# BaseFunctions.net
KiCad netlist of a schematic drawn in Altium Designer
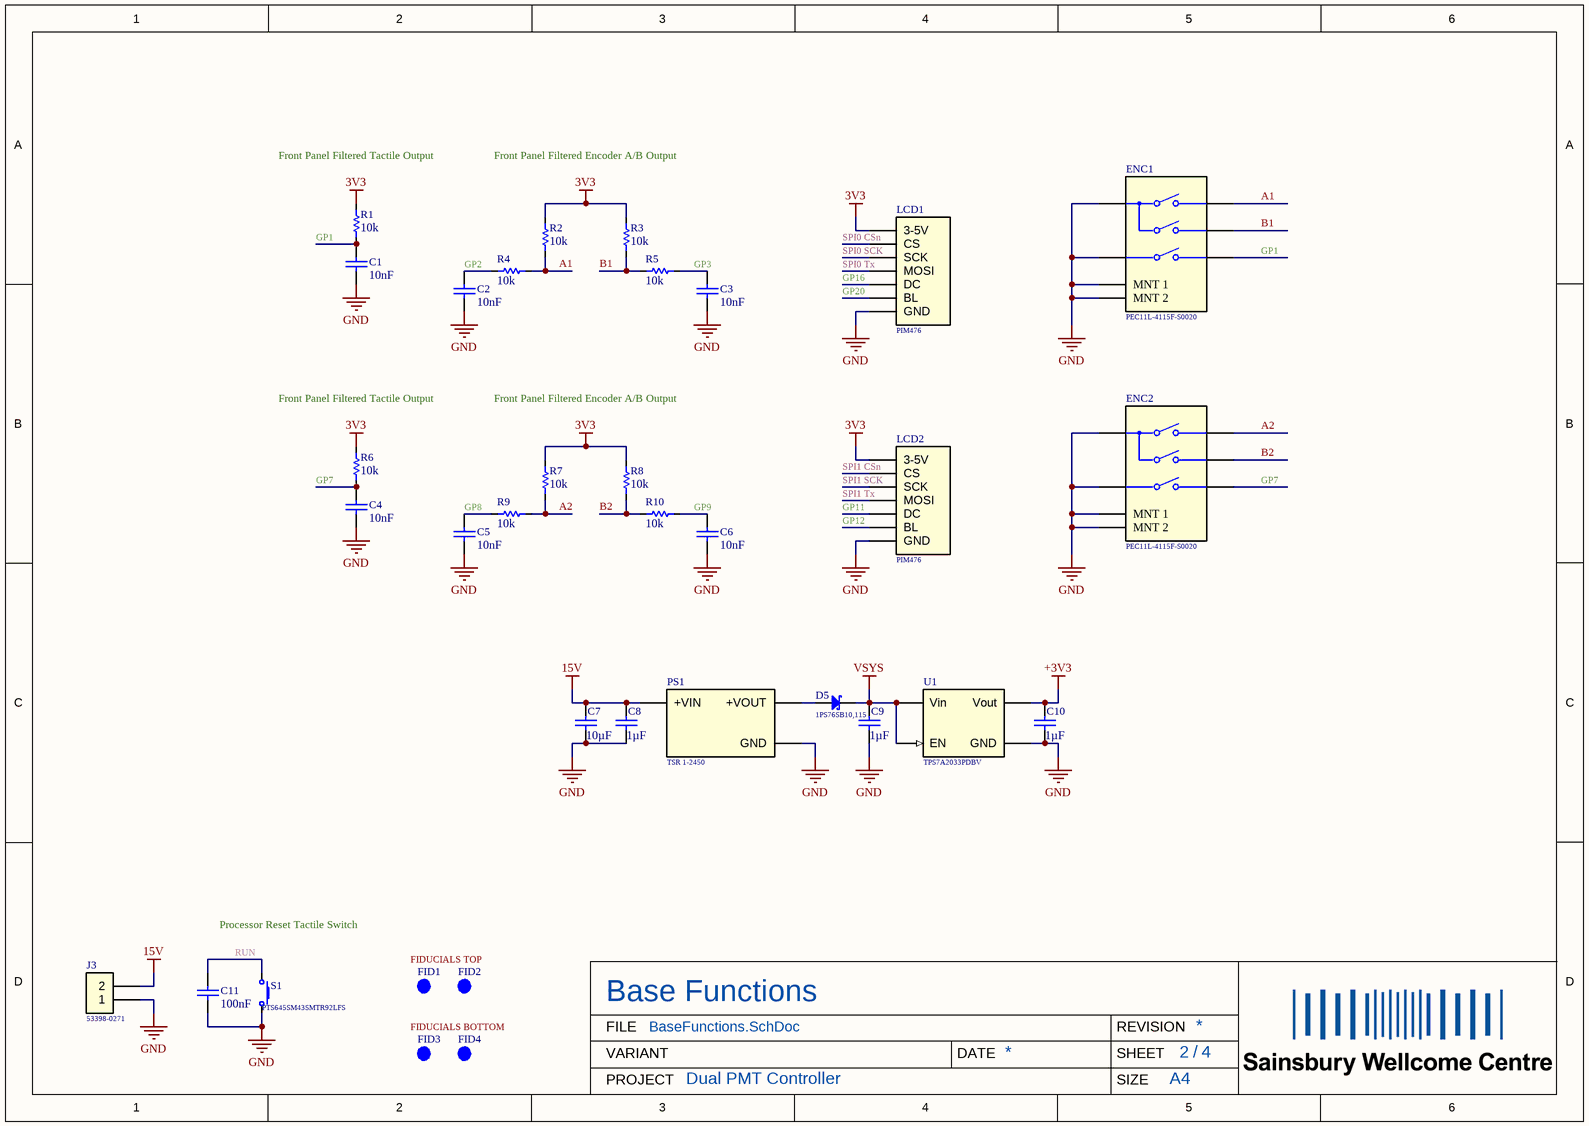
[diagram p0: BaseFunctions.SchDoc]

(export (version "E")
  (design (tool "Eeschema 10.0.6"))
  (components
    (comp (ref "C1")
      (value "10nF")
      (footprint "CAPC1608X90X35NL15T15")
      (description "0.01µF ±10% 100V Ceramic Capacitor X7R 0603 (1608 Metric)")
      (fields (field (name "TOLERANCE") "10%") (field (name "Comment") "C0603-10nF-100V-10%-X7R"))
      (libsource (lib "Sainsbury Wellcome Centre") (part "Cap"))
    )
    (comp (ref "C2")
      (value "10nF")
      (footprint "CAPC1608X90X35NL15T15")
      (description "0.01µF ±10% 100V Ceramic Capacitor X7R 0603 (1608 Metric)")
      (fields (field (name "TOLERANCE") "10%") (field (name "Comment") "C0603-10nF-100V-10%-X7R"))
      (libsource (lib "Sainsbury Wellcome Centre") (part "Cap"))
    )
    (comp (ref "C3")
      (value "10nF")
      (footprint "CAPC1608X90X35NL15T15")
      (description "0.01µF ±10% 100V Ceramic Capacitor X7R 0603 (1608 Metric)")
      (fields (field (name "TOLERANCE") "10%") (field (name "Comment") "C0603-10nF-100V-10%-X7R"))
      (libsource (lib "Sainsbury Wellcome Centre") (part "Cap"))
    )
    (comp (ref "C4")
      (value "10nF")
      (footprint "CAPC1608X90X35NL15T15")
      (description "0.01µF ±10% 100V Ceramic Capacitor X7R 0603 (1608 Metric)")
      (fields (field (name "TOLERANCE") "10%") (field (name "Comment") "C0603-10nF-100V-10%-X7R"))
      (libsource (lib "Sainsbury Wellcome Centre") (part "Cap"))
    )
    (comp (ref "C5")
      (value "10nF")
      (footprint "CAPC1608X90X35NL15T15")
      (description "0.01µF ±10% 100V Ceramic Capacitor X7R 0603 (1608 Metric)")
      (fields (field (name "TOLERANCE") "10%") (field (name "Comment") "C0603-10nF-100V-10%-X7R"))
      (libsource (lib "Sainsbury Wellcome Centre") (part "Cap"))
    )
    (comp (ref "C6")
      (value "10nF")
      (footprint "CAPC1608X90X35NL15T15")
      (description "0.01µF ±10% 100V Ceramic Capacitor X7R 0603 (1608 Metric)")
      (fields (field (name "TOLERANCE") "10%") (field (name "Comment") "C0603-10nF-100V-10%-X7R"))
      (libsource (lib "Sainsbury Wellcome Centre") (part "Cap"))
    )
    (comp (ref "C7")
      (value "10µF")
      (footprint "CAPC3225X279X50NL20T25")
      (description "10uF ±10% 50V Ceramic Capacitor X7R 1210 (3225 Metric)")
      (fields (field (name "TOLERANCE") "10%") (field (name "Comment") "C1210-10uF-50V-10%-X7R"))
      (libsource (lib "Sainsbury Wellcome Centre") (part "Cap"))
    )
    (comp (ref "C8")
      (value "1µF")
      (footprint "FP-GRM188-0_1-e0_2_0_5-IPC_B")
      (description "1µF ±10% 25V Ceramic Capacitor X7R 0603 (1608 Metric)")
      (fields (field (name "TOLERANCE") "10%") (field (name "VOLTAGE") "25V"))
      (libsource (lib "Sainsbury Wellcome Centre") (part "Cap"))
    )
    (comp (ref "C9")
      (value "1µF")
      (footprint "FP-GRM188-0_1-e0_2_0_5-IPC_B")
      (description "1µF ±10% 25V Ceramic Capacitor X7R 0603 (1608 Metric)")
      (fields (field (name "TOLERANCE") "10%") (field (name "VOLTAGE") "25V"))
      (libsource (lib "Sainsbury Wellcome Centre") (part "Cap"))
    )
    (comp (ref "C10")
      (value "1µF")
      (footprint "FP-GRM188-0_1-e0_2_0_5-IPC_B")
      (description "1µF ±10% 25V Ceramic Capacitor X7R 0603 (1608 Metric)")
      (fields (field (name "TOLERANCE") "10%") (field (name "VOLTAGE") "25V"))
      (libsource (lib "Sainsbury Wellcome Centre") (part "Cap"))
    )
    (comp (ref "C11")
      (value "100nF")
      (footprint "FP-GRM188-0_1-e0_2_0_5-IPC_B")
      (description "0.1µF ±10% 100V Ceramic Capacitor X7R 0603 (1608 Metric)")
      (fields (field (name "TOLERANCE") "10%") (field (name "VOLTAGE") "100V"))
      (libsource (lib "Sainsbury Wellcome Centre") (part "Cap"))
    )
    (comp (ref "D5")
      (value "1PS76SB10,115")
      (footprint "FP-SOD323F-MFG")
      (description "Rectifier Diode, Schottky, 1 Phase, 1 Element, 0.2A, Silicon")
      (fields (field (name "PARTNUMBER") "1PS76SB10,115"))
      (libsource (lib "Sainsbury Wellcome Centre") (part "Schottky-C1A2"))
    )
    (comp (ref "ENC1")
      (value "PEC11L-4115F-S0020")
      (footprint "FP-PEC11L-4115F-S0020-MFG")
      (description "LOW PROFILE ENCODER, 11 MM, CONTACT RATING 10 MA - 5 VDC")
      (libsource (lib "Sainsbury Wellcome Centre") (part "PEC11L-4xxxF-Sxxxx"))
    )
    (comp (ref "ENC2")
      (value "PEC11L-4115F-S0020")
      (footprint "FP-PEC11L-4115F-S0020-MFG")
      (description "LOW PROFILE ENCODER, 11 MM, CONTACT RATING 10 MA - 5 VDC")
      (libsource (lib "Sainsbury Wellcome Centre") (part "PEC11L-4xxxF-Sxxxx"))
    )
    (comp (ref "FID1")
      (value "FID-ROUND")
      (footprint "Fid_Round")
      (description "Round Fiducial")
      (libsource (lib "Sainsbury Wellcome Centre") (part "Fid_Round"))
    )
    (comp (ref "FID2")
      (value "FID-ROUND")
      (footprint "Fid_Round")
      (description "Round Fiducial")
      (libsource (lib "Sainsbury Wellcome Centre") (part "Fid_Round"))
    )
    (comp (ref "FID3")
      (value "FID-ROUND")
      (footprint "Fid_Round")
      (description "Round Fiducial")
      (libsource (lib "Sainsbury Wellcome Centre") (part "Fid_Round"))
    )
    (comp (ref "FID4")
      (value "FID-ROUND")
      (footprint "Fid_Round")
      (description "Round Fiducial")
      (libsource (lib "Sainsbury Wellcome Centre") (part "Fid_Round"))
    )
    (comp (ref "J3")
      (value "53398-0271")
      (footprint "MOLX-53398-0271_V")
      (libsource (lib "Sainsbury Wellcome Centre") (part "Jack 2x1"))
    )
    (comp (ref "LCD1")
      (value "PIM476")
      (footprint "LCD-PIM476-TSW - 2mm9 standoff")
      (description "1.3\" Spi Colour Lcd (240X240) Breakout")
      (libsource (lib "Sainsbury Wellcome Centre") (part "LCD-PIM476"))
    )
    (comp (ref "LCD2")
      (value "PIM476")
      (footprint "LCD-PIM476-TSW - 2mm9 standoff")
      (description "1.3\" Spi Colour Lcd (240X240) Breakout")
      (libsource (lib "Sainsbury Wellcome Centre") (part "LCD-PIM476"))
    )
    (comp (ref "PS1")
      (value "TSR 1-2450")
      (footprint "CONV_TSR_1-2433")
      (description "DC/DC Converter, ITE, 1 Output, 5 W, 5 V, 1 A, TSR 1 Series")
      (libsource (lib "Sainsbury Wellcome Centre") (part "TRACO-TSR1-2433-SIP-3"))
    )
    (comp (ref "R1")
      (value "10k")
      (footprint "FP-CPF0603-IPC_B")
      (description "Surface Mount Resistor 10k Ohm 1/16 W 0.1% 0603 (1608 Metric)")
      (fields (field (name "TOLERANCE") "0.1%") (field (name "Comment") "R0603-10k-1/16W-0.1%"))
      (libsource (lib "Sainsbury Wellcome Centre") (part "Res"))
    )
    (comp (ref "R2")
      (value "10k")
      (footprint "FP-CPF0603-IPC_B")
      (description "Surface Mount Resistor 10k Ohm 1/16 W 0.1% 0603 (1608 Metric)")
      (fields (field (name "TOLERANCE") "0.1%") (field (name "Comment") "R0603-10k-1/16W-0.1%"))
      (libsource (lib "Sainsbury Wellcome Centre") (part "Res"))
    )
    (comp (ref "R3")
      (value "10k")
      (footprint "FP-CPF0603-IPC_B")
      (description "Surface Mount Resistor 10k Ohm 1/16 W 0.1% 0603 (1608 Metric)")
      (fields (field (name "TOLERANCE") "0.1%") (field (name "Comment") "R0603-10k-1/16W-0.1%"))
      (libsource (lib "Sainsbury Wellcome Centre") (part "Res"))
    )
    (comp (ref "R4")
      (value "10k")
      (footprint "FP-CPF0603-IPC_B")
      (description "Surface Mount Resistor 10k Ohm 1/16 W 0.1% 0603 (1608 Metric)")
      (fields (field (name "TOLERANCE") "0.1%") (field (name "Comment") "R0603-10k-1/16W-0.1%"))
      (libsource (lib "Sainsbury Wellcome Centre") (part "Res"))
    )
    (comp (ref "R5")
      (value "10k")
      (footprint "FP-CPF0603-IPC_B")
      (description "Surface Mount Resistor 10k Ohm 1/16 W 0.1% 0603 (1608 Metric)")
      (fields (field (name "TOLERANCE") "0.1%") (field (name "Comment") "R0603-10k-1/16W-0.1%"))
      (libsource (lib "Sainsbury Wellcome Centre") (part "Res"))
    )
    (comp (ref "R6")
      (value "10k")
      (footprint "FP-CPF0603-IPC_B")
      (description "Surface Mount Resistor 10k Ohm 1/16 W 0.1% 0603 (1608 Metric)")
      (fields (field (name "TOLERANCE") "0.1%") (field (name "Comment") "R0603-10k-1/16W-0.1%"))
      (libsource (lib "Sainsbury Wellcome Centre") (part "Res"))
    )
    (comp (ref "R7")
      (value "10k")
      (footprint "FP-CPF0603-IPC_B")
      (description "Surface Mount Resistor 10k Ohm 1/16 W 0.1% 0603 (1608 Metric)")
      (fields (field (name "TOLERANCE") "0.1%") (field (name "Comment") "R0603-10k-1/16W-0.1%"))
      (libsource (lib "Sainsbury Wellcome Centre") (part "Res"))
    )
    (comp (ref "R8")
      (value "10k")
      (footprint "FP-CPF0603-IPC_B")
      (description "Surface Mount Resistor 10k Ohm 1/16 W 0.1% 0603 (1608 Metric)")
      (fields (field (name "TOLERANCE") "0.1%") (field (name "Comment") "R0603-10k-1/16W-0.1%"))
      (libsource (lib "Sainsbury Wellcome Centre") (part "Res"))
    )
    (comp (ref "R9")
      (value "10k")
      (footprint "FP-CPF0603-IPC_B")
      (description "Surface Mount Resistor 10k Ohm 1/16 W 0.1% 0603 (1608 Metric)")
      (fields (field (name "TOLERANCE") "0.1%") (field (name "Comment") "R0603-10k-1/16W-0.1%"))
      (libsource (lib "Sainsbury Wellcome Centre") (part "Res"))
    )
    (comp (ref "R10")
      (value "10k")
      (footprint "FP-CPF0603-IPC_B")
      (description "Surface Mount Resistor 10k Ohm 1/16 W 0.1% 0603 (1608 Metric)")
      (fields (field (name "TOLERANCE") "0.1%") (field (name "Comment") "R0603-10k-1/16W-0.1%"))
      (libsource (lib "Sainsbury Wellcome Centre") (part "Res"))
    )
    (comp (ref "S1")
      (value "PTS645SM43SMTR92LFS")
      (footprint "FP-PTS645SM43SMTR92LFS-MFG")
      (libsource (lib "Sainsbury Wellcome Centre") (part "Tactile Switch SPST N.O."))
    )
    (comp (ref "U1")
      (value "TPS7A2033PDBV")
      (footprint "FP-DBV0005A-IPC_B")
      (description "Fixed Positive LDO Regulator, 3.3V, 0.14V Dropout, PDSO5")
      (libsource (lib "Sainsbury Wellcome Centre") (part "TPS7A2033PDBV"))
    )
  )
  (nets
    (net (code "1") (name "+3V3") (class "Default")
      (node (ref "C10") (pin "2") (pinfunction "2_2") (pintype "passive"))
      (node (ref "U1") (pin "5") (pinfunction "Vout_5") (pintype "power_in"))
    )
    (net (code "2") (name "/A1") (class "Default")
      (node (ref "ENC1") (pin "A") (pinfunction "CHANNEL_A_A") (pintype "passive"))
      (node (ref "R2") (pin "1") (pinfunction "1_1") (pintype "passive"))
      (node (ref "R4") (pin "1") (pinfunction "1_1") (pintype "passive"))
    )
    (net (code "3") (name "/A2") (class "Default")
      (node (ref "ENC2") (pin "A") (pinfunction "CHANNEL_A_A") (pintype "passive"))
      (node (ref "R7") (pin "1") (pinfunction "1_1") (pintype "passive"))
      (node (ref "R9") (pin "1") (pinfunction "1_1") (pintype "passive"))
    )
    (net (code "4") (name "/B1") (class "Default")
      (node (ref "ENC1") (pin "B") (pinfunction "CHANNEL_B_B") (pintype "passive"))
      (node (ref "R3") (pin "1") (pinfunction "1_1") (pintype "passive"))
      (node (ref "R5") (pin "2") (pinfunction "2_2") (pintype "passive"))
    )
    (net (code "5") (name "/B2") (class "Default")
      (node (ref "ENC2") (pin "B") (pinfunction "CHANNEL_B_B") (pintype "passive"))
      (node (ref "R10") (pin "2") (pinfunction "2_2") (pintype "passive"))
      (node (ref "R8") (pin "1") (pinfunction "1_1") (pintype "passive"))
    )
    (net (code "6") (name "/GP1") (class "Default")
      (node (ref "C1") (pin "2") (pinfunction "2_2") (pintype "passive"))
      (node (ref "ENC1") (pin "2") (pinfunction "2_2") (pintype "passive"))
      (node (ref "R1") (pin "1") (pinfunction "1_1") (pintype "passive"))
    )
    (net (code "7") (name "/GP2") (class "Default")
      (node (ref "C2") (pin "2") (pinfunction "2_2") (pintype "passive"))
      (node (ref "R4") (pin "2") (pinfunction "2_2") (pintype "passive"))
    )
    (net (code "8") (name "/GP3") (class "Default")
      (node (ref "C3") (pin "2") (pinfunction "2_2") (pintype "passive"))
      (node (ref "R5") (pin "1") (pinfunction "1_1") (pintype "passive"))
    )
    (net (code "9") (name "/GP7") (class "Default")
      (node (ref "C4") (pin "2") (pinfunction "2_2") (pintype "passive"))
      (node (ref "ENC2") (pin "2") (pinfunction "2_2") (pintype "passive"))
      (node (ref "R6") (pin "1") (pinfunction "1_1") (pintype "passive"))
    )
    (net (code "10") (name "/GP8") (class "Default")
      (node (ref "C5") (pin "2") (pinfunction "2_2") (pintype "passive"))
      (node (ref "R9") (pin "2") (pinfunction "2_2") (pintype "passive"))
    )
    (net (code "11") (name "/GP9") (class "Default")
      (node (ref "C6") (pin "2") (pinfunction "2_2") (pintype "passive"))
      (node (ref "R10") (pin "1") (pinfunction "1_1") (pintype "passive"))
    )
    (net (code "12") (name "/GP11") (class "Default")
      (node (ref "LCD2") (pin "5") (pinfunction "DC_5") (pintype "passive"))
    )
    (net (code "13") (name "/GP12") (class "Default")
      (node (ref "LCD2") (pin "6") (pinfunction "BL_6") (pintype "passive"))
    )
    (net (code "14") (name "/GP16") (class "Default")
      (node (ref "LCD1") (pin "5") (pinfunction "DC_5") (pintype "passive"))
    )
    (net (code "15") (name "/GP20") (class "Default")
      (node (ref "LCD1") (pin "6") (pinfunction "BL_6") (pintype "passive"))
    )
    (net (code "16") (name "/RUN") (class "Default")
      (node (ref "C11") (pin "2") (pinfunction "2_2") (pintype "passive"))
      (node (ref "S1") (pin "2") (pinfunction "2_2") (pintype "passive"))
    )
    (net (code "17") (name "/SPI0 CSn") (class "Default")
      (node (ref "LCD1") (pin "2") (pinfunction "CS_2") (pintype "passive"))
    )
    (net (code "18") (name "/SPI0 SCK") (class "Default")
      (node (ref "LCD1") (pin "3") (pinfunction "SCK_3") (pintype "passive"))
    )
    (net (code "19") (name "/SPI0 Tx") (class "Default")
      (node (ref "LCD1") (pin "4") (pinfunction "MOSI_4") (pintype "passive"))
    )
    (net (code "20") (name "/SPI1 CSn") (class "Default")
      (node (ref "LCD2") (pin "2") (pinfunction "CS_2") (pintype "passive"))
    )
    (net (code "21") (name "/SPI1 SCK") (class "Default")
      (node (ref "LCD2") (pin "3") (pinfunction "SCK_3") (pintype "passive"))
    )
    (net (code "22") (name "/SPI1 Tx") (class "Default")
      (node (ref "LCD2") (pin "4") (pinfunction "MOSI_4") (pintype "passive"))
    )
    (net (code "23") (name "3V3") (class "Default")
      (node (ref "LCD1") (pin "1") (pinfunction "3-5V_1") (pintype "passive"))
      (node (ref "LCD2") (pin "1") (pinfunction "3-5V_1") (pintype "passive"))
      (node (ref "R1") (pin "2") (pinfunction "2_2") (pintype "passive"))
      (node (ref "R2") (pin "2") (pinfunction "2_2") (pintype "passive"))
      (node (ref "R3") (pin "2") (pinfunction "2_2") (pintype "passive"))
      (node (ref "R6") (pin "2") (pinfunction "2_2") (pintype "passive"))
      (node (ref "R7") (pin "2") (pinfunction "2_2") (pintype "passive"))
      (node (ref "R8") (pin "2") (pinfunction "2_2") (pintype "passive"))
    )
    (net (code "24") (name "15V") (class "Default")
      (node (ref "C7") (pin "2") (pinfunction "2_2") (pintype "passive"))
      (node (ref "C8") (pin "2") (pinfunction "2_2") (pintype "passive"))
      (node (ref "J3") (pin "2") (pinfunction "2_2") (pintype "passive"))
      (node (ref "PS1") (pin "1") (pinfunction "+VIN_1") (pintype "power_in"))
    )
    (net (code "25") (name "GND") (class "Default")
      (node (ref "C1") (pin "1") (pinfunction "1_1") (pintype "passive"))
      (node (ref "C10") (pin "1") (pinfunction "1_1") (pintype "passive"))
      (node (ref "C11") (pin "1") (pinfunction "1_1") (pintype "passive"))
      (node (ref "C2") (pin "1") (pinfunction "1_1") (pintype "passive"))
      (node (ref "C3") (pin "1") (pinfunction "1_1") (pintype "passive"))
      (node (ref "C4") (pin "1") (pinfunction "1_1") (pintype "passive"))
      (node (ref "C5") (pin "1") (pinfunction "1_1") (pintype "passive"))
      (node (ref "C6") (pin "1") (pinfunction "1_1") (pintype "passive"))
      (node (ref "C7") (pin "1") (pinfunction "1_1") (pintype "passive"))
      (node (ref "C8") (pin "1") (pinfunction "1_1") (pintype "passive"))
      (node (ref "C9") (pin "1") (pinfunction "1_1") (pintype "passive"))
      (node (ref "ENC1") (pin "1") (pinfunction "1_1") (pintype "passive"))
      (node (ref "ENC1") (pin "3") (pinfunction "MNT_1_3") (pintype "passive"))
      (node (ref "ENC1") (pin "4") (pinfunction "MNT_2_4") (pintype "passive"))
      (node (ref "ENC1") (pin "C") (pinfunction "COMMON_C") (pintype "passive"))
      (node (ref "ENC2") (pin "1") (pinfunction "1_1") (pintype "passive"))
      (node (ref "ENC2") (pin "3") (pinfunction "MNT_1_3") (pintype "passive"))
      (node (ref "ENC2") (pin "4") (pinfunction "MNT_2_4") (pintype "passive"))
      (node (ref "ENC2") (pin "C") (pinfunction "COMMON_C") (pintype "passive"))
      (node (ref "J3") (pin "1") (pinfunction "1_1") (pintype "passive"))
      (node (ref "LCD1") (pin "7") (pinfunction "GND_7") (pintype "passive"))
      (node (ref "LCD2") (pin "7") (pinfunction "GND_7") (pintype "passive"))
      (node (ref "PS1") (pin "2") (pinfunction "GND_2") (pintype "power_in"))
      (node (ref "S1") (pin "1") (pinfunction "1_1") (pintype "passive"))
      (node (ref "U1") (pin "2") (pinfunction "GND_2") (pintype "power_in"))
    )
    (net (code "26") (name "Net-(D5-A)") (class "Default")
      (node (ref "D5") (pin "2") (pinfunction "A_2") (pintype "passive"))
      (node (ref "PS1") (pin "3") (pinfunction "+VOUT_3") (pintype "power_in"))
    )
    (net (code "27") (name "VSYS") (class "Default")
      (node (ref "C9") (pin "2") (pinfunction "2_2") (pintype "passive"))
      (node (ref "D5") (pin "1") (pinfunction "C_1") (pintype "passive"))
      (node (ref "U1") (pin "1") (pinfunction "Vin_1") (pintype "power_in"))
      (node (ref "U1") (pin "3") (pinfunction "EN_3") (pintype "input"))
    )
  )
)
